# EFR32_IO.net
KiCad netlist of a schematic drawn in Altium Designer
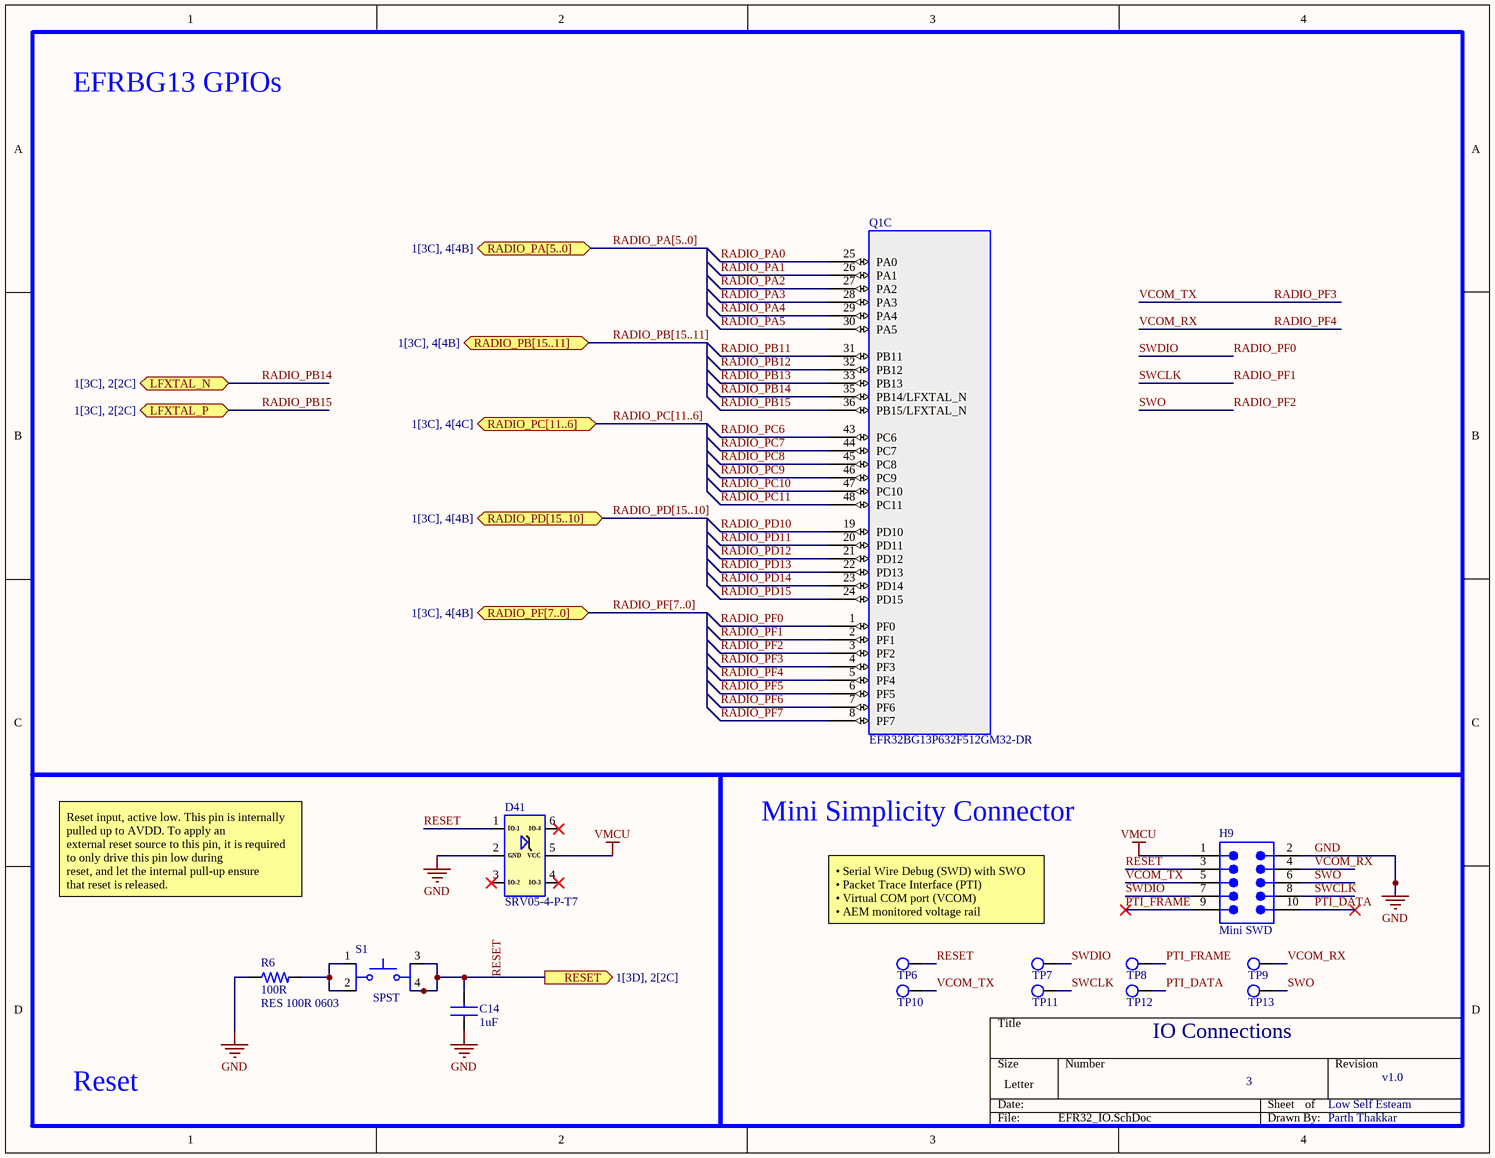
[diagram p0: EFR32_IO.SchDoc]

(export (version "E")
  (design (tool "Eeschema 10.0.6"))
  (components
    (comp (ref "C14")
      (value "1uF")
      (footprint "Capacitor 0603")
      (fields
        (field (name "MANUFACTURER") "Murata")
        (field (name "MANUFACTURER PART NUMBER") "GRM188R61A105KA61D")
        (field (name "Comment") "CAP 1uF 10V 0603")
      )
      (libsource (lib "Keyboard_parts") (part "CAP 1uF 10V 0603"))
    )
    (comp (ref "D41")
      (value "SRV05-4-P-T7")
      (footprint "TVS")
      (description "Trans Voltage Suppressor Diode, 300W, 5V V(RWM), Unidirectional, 1 Element, Silicon")
      (fields (field (name "LCSC PART#") "C85364") (field (name "MANUFACTURER") "Semtech"))
      (libsource (lib "Keyboard_parts") (part "D_TVS_Diode"))
    )
    (comp (ref "H9")
      (value "Mini SWD")
      (footprint "Mini Simplicity Connector")
      (description "Mini SWD 0.05\" Pitch Connector - 10 Pin SMT Box Header")
      (fields
        (field (name "MANUFACTURER") "Adafruit Industries")
        (field (name "MANUFACTURER PART NUMBER") "4048")
      )
      (libsource (lib "Keyboard_parts") (part "Debug Connector Mini SWD - 0.05{dblquote}"))
    )
    (comp (ref "Q1")
      (value "EFR32BG13P632F512GM32-DR")
      (footprint "EFR32BG")
      (description "BLue Gecko")
      (fields (field (name "MANUFACTURER") "Silicon Labs"))
      (libsource (lib "Keyboard_parts") (part "EFR32BG13P632F512GM32-DR"))
    )
    (comp (ref "R6")
      (value "RES 100R 0603")
      (footprint "Resistor 0603")
      (fields
        (field (name "MANUFACTURER") "Yageo")
        (field (name "MANUFACTURER PART NUMBER") "RC0603FR-07100RL")
        (field (name "TOLERANCE") "1%")
        (field (name "ALTIUM_VALUE") "100R")
      )
      (libsource (lib "Keyboard_parts") (part "RES 100R 0603"))
    )
    (comp (ref "S1")
      (value "SPST")
      (footprint "SPST")
      (fields
        (field (name "MANUFACTURER") "E-Switch")
        (field (name "MANUFACTURER PART NUMBER") "TL3301NF260QG")
      )
      (libsource (lib "Keyboard_parts") (part "SPST"))
    )
    (comp (ref "TP6")
      (value "Test point")
      (footprint "Test Point")
      (libsource (lib "Keyboard_parts") (part "Test point"))
    )
    (comp (ref "TP7")
      (value "Test point")
      (footprint "Test Point")
      (libsource (lib "Keyboard_parts") (part "Test point"))
    )
    (comp (ref "TP8")
      (value "Test point")
      (footprint "Test Point")
      (libsource (lib "Keyboard_parts") (part "Test point"))
    )
    (comp (ref "TP9")
      (value "Test point")
      (footprint "Test Point")
      (libsource (lib "Keyboard_parts") (part "Test point"))
    )
    (comp (ref "TP10")
      (value "Test point")
      (footprint "Test Point")
      (libsource (lib "Keyboard_parts") (part "Test point"))
    )
    (comp (ref "TP11")
      (value "Test point")
      (footprint "Test Point")
      (libsource (lib "Keyboard_parts") (part "Test point"))
    )
    (comp (ref "TP12")
      (value "Test point")
      (footprint "Test Point")
      (libsource (lib "Keyboard_parts") (part "Test point"))
    )
    (comp (ref "TP13")
      (value "Test point")
      (footprint "Test Point")
      (libsource (lib "Keyboard_parts") (part "Test point"))
    )
  )
  (nets
    (net (code "1") (name "/PTI_DATA") (class "Default")
      (node (ref "H9") (pin "10") (pinfunction "10_10") (pintype "passive"))
      (node (ref "TP12") (pin "1") (pinfunction "1_1") (pintype "passive"))
    )
    (net (code "2") (name "/PTI_FRAME") (class "Default")
      (node (ref "H9") (pin "9") (pinfunction "9_9") (pintype "passive"))
      (node (ref "TP8") (pin "1") (pinfunction "1_1") (pintype "passive"))
    )
    (net (code "3") (name "/RADIO_PA0") (class "Default")
      (node (ref "Q1") (pin "25") (pinfunction "PA0_25") (pintype "bidirectional"))
    )
    (net (code "4") (name "/RADIO_PA1") (class "Default")
      (node (ref "Q1") (pin "26") (pinfunction "PA1_26") (pintype "bidirectional"))
    )
    (net (code "5") (name "/RADIO_PA2") (class "Default")
      (node (ref "Q1") (pin "27") (pinfunction "PA2_27") (pintype "bidirectional"))
    )
    (net (code "6") (name "/RADIO_PA3") (class "Default")
      (node (ref "Q1") (pin "28") (pinfunction "PA3_28") (pintype "bidirectional"))
    )
    (net (code "7") (name "/RADIO_PA4") (class "Default")
      (node (ref "Q1") (pin "29") (pinfunction "PA4_29") (pintype "bidirectional"))
    )
    (net (code "8") (name "/RADIO_PA5") (class "Default")
      (node (ref "Q1") (pin "30") (pinfunction "PA5_30") (pintype "bidirectional"))
    )
    (net (code "10") (name "/RADIO_PB11") (class "Default")
      (node (ref "Q1") (pin "31") (pinfunction "PB11_31") (pintype "bidirectional"))
    )
    (net (code "11") (name "/RADIO_PB12") (class "Default")
      (node (ref "Q1") (pin "32") (pinfunction "PB12_32") (pintype "bidirectional"))
    )
    (net (code "12") (name "/RADIO_PB13") (class "Default")
      (node (ref "Q1") (pin "33") (pinfunction "PB13_33") (pintype "bidirectional"))
    )
    (net (code "13") (name "/RADIO_PB14") (class "Default")
      (node (ref "Q1") (pin "35") (pinfunction "PB14/LFXTAL_N_35") (pintype "bidirectional"))
    )
    (net (code "14") (name "/RADIO_PB15") (class "Default")
      (node (ref "Q1") (pin "36") (pinfunction "PB15/LFXTAL_N_36") (pintype "bidirectional"))
    )
    (net (code "16") (name "/RADIO_PC6") (class "Default")
      (node (ref "Q1") (pin "43") (pinfunction "PC6_43") (pintype "bidirectional"))
    )
    (net (code "17") (name "/RADIO_PC7") (class "Default")
      (node (ref "Q1") (pin "44") (pinfunction "PC7_44") (pintype "bidirectional"))
    )
    (net (code "18") (name "/RADIO_PC8") (class "Default")
      (node (ref "Q1") (pin "45") (pinfunction "PC8_45") (pintype "bidirectional"))
    )
    (net (code "19") (name "/RADIO_PC9") (class "Default")
      (node (ref "Q1") (pin "46") (pinfunction "PC9_46") (pintype "bidirectional"))
    )
    (net (code "20") (name "/RADIO_PC10") (class "Default")
      (node (ref "Q1") (pin "47") (pinfunction "PC10_47") (pintype "bidirectional"))
    )
    (net (code "21") (name "/RADIO_PC11") (class "Default")
      (node (ref "Q1") (pin "48") (pinfunction "PC11_48") (pintype "bidirectional"))
    )
    (net (code "23") (name "/RADIO_PD10") (class "Default")
      (node (ref "Q1") (pin "19") (pinfunction "PD10_19") (pintype "bidirectional"))
    )
    (net (code "24") (name "/RADIO_PD11") (class "Default")
      (node (ref "Q1") (pin "20") (pinfunction "PD11_20") (pintype "bidirectional"))
    )
    (net (code "25") (name "/RADIO_PD12") (class "Default")
      (node (ref "Q1") (pin "21") (pinfunction "PD12_21") (pintype "bidirectional"))
    )
    (net (code "26") (name "/RADIO_PD13") (class "Default")
      (node (ref "Q1") (pin "22") (pinfunction "PD13_22") (pintype "bidirectional"))
    )
    (net (code "27") (name "/RADIO_PD14") (class "Default")
      (node (ref "Q1") (pin "23") (pinfunction "PD14_23") (pintype "bidirectional"))
    )
    (net (code "28") (name "/RADIO_PD15") (class "Default")
      (node (ref "Q1") (pin "24") (pinfunction "PD15_24") (pintype "bidirectional"))
    )
    (net (code "30") (name "/RADIO_PF0") (class "Default")
      (node (ref "H9") (pin "7") (pinfunction "7_7") (pintype "passive"))
      (node (ref "Q1") (pin "1") (pinfunction "PF0_1") (pintype "bidirectional"))
      (node (ref "TP7") (pin "1") (pinfunction "1_1") (pintype "passive"))
    )
    (net (code "31") (name "/RADIO_PF1") (class "Default")
      (node (ref "H9") (pin "8") (pinfunction "8_8") (pintype "passive"))
      (node (ref "Q1") (pin "2") (pinfunction "PF1_2") (pintype "bidirectional"))
      (node (ref "TP11") (pin "1") (pinfunction "1_1") (pintype "passive"))
    )
    (net (code "32") (name "/RADIO_PF2") (class "Default")
      (node (ref "H9") (pin "6") (pinfunction "6_6") (pintype "passive"))
      (node (ref "Q1") (pin "3") (pinfunction "PF2_3") (pintype "bidirectional"))
      (node (ref "TP13") (pin "1") (pinfunction "1_1") (pintype "passive"))
    )
    (net (code "33") (name "/RADIO_PF3") (class "Default")
      (node (ref "H9") (pin "5") (pinfunction "5_5") (pintype "passive"))
      (node (ref "Q1") (pin "4") (pinfunction "PF3_4") (pintype "bidirectional"))
      (node (ref "TP10") (pin "1") (pinfunction "1_1") (pintype "passive"))
    )
    (net (code "34") (name "/RADIO_PF4") (class "Default")
      (node (ref "H9") (pin "4") (pinfunction "4_4") (pintype "passive"))
      (node (ref "Q1") (pin "5") (pinfunction "PF4_5") (pintype "bidirectional"))
      (node (ref "TP9") (pin "1") (pinfunction "1_1") (pintype "passive"))
    )
    (net (code "35") (name "/RADIO_PF5") (class "Default")
      (node (ref "Q1") (pin "6") (pinfunction "PF5_6") (pintype "bidirectional"))
    )
    (net (code "36") (name "/RADIO_PF6") (class "Default")
      (node (ref "Q1") (pin "7") (pinfunction "PF6_7") (pintype "bidirectional"))
    )
    (net (code "37") (name "/RADIO_PF7") (class "Default")
      (node (ref "Q1") (pin "8") (pinfunction "PF7_8") (pintype "bidirectional"))
    )
    (net (code "39") (name "/RESET") (class "Default")
      (node (ref "C14") (pin "1") (pinfunction "1_1") (pintype "passive"))
      (node (ref "D41") (pin "1") (pinfunction "IO-1_1") (pintype "passive"))
      (node (ref "H9") (pin "3") (pinfunction "3_3") (pintype "passive"))
      (node (ref "S1") (pin "3") (pinfunction "3_3") (pintype "passive"))
      (node (ref "S1") (pin "4") (pinfunction "4_4") (pintype "passive"))
      (node (ref "TP6") (pin "1") (pinfunction "1_1") (pintype "passive"))
    )
    (net (code "40") (name "GND") (class "Default")
      (node (ref "C14") (pin "2") (pinfunction "2_2") (pintype "passive"))
      (node (ref "D41") (pin "2") (pinfunction "GND_2") (pintype "passive"))
      (node (ref "H9") (pin "2") (pinfunction "2_2") (pintype "passive"))
      (node (ref "R6") (pin "1") (pinfunction "1_1") (pintype "passive"))
    )
    (net (code "41") (name "Net-(R6-Pad2)") (class "Default")
      (node (ref "R6") (pin "2") (pinfunction "2_2") (pintype "passive"))
      (node (ref "S1") (pin "1") (pinfunction "1_1") (pintype "passive"))
      (node (ref "S1") (pin "2") (pinfunction "2_2") (pintype "passive"))
    )
    (net (code "42") (name "VMCU") (class "Default")
      (node (ref "D41") (pin "5") (pinfunction "VCC_5") (pintype "passive"))
      (node (ref "H9") (pin "1") (pinfunction "1_1") (pintype "passive"))
    )
    (net (code "43") (name "unconnected-(D41-IO-2-Pad3)") (class "Default")
      (node (ref "D41") (pin "3") (pinfunction "IO-2_3") (pintype "passive+no_connect"))
    )
    (net (code "44") (name "unconnected-(D41-IO-3-Pad4)") (class "Default")
      (node (ref "D41") (pin "4") (pinfunction "IO-3_4") (pintype "passive+no_connect"))
    )
    (net (code "45") (name "unconnected-(D41-IO-4-Pad6)") (class "Default")
      (node (ref "D41") (pin "6") (pinfunction "IO-4_6") (pintype "passive+no_connect"))
    )
  )
)
